# Final_5_2.net
KiCad netlist of a schematic drawn in EAGLE
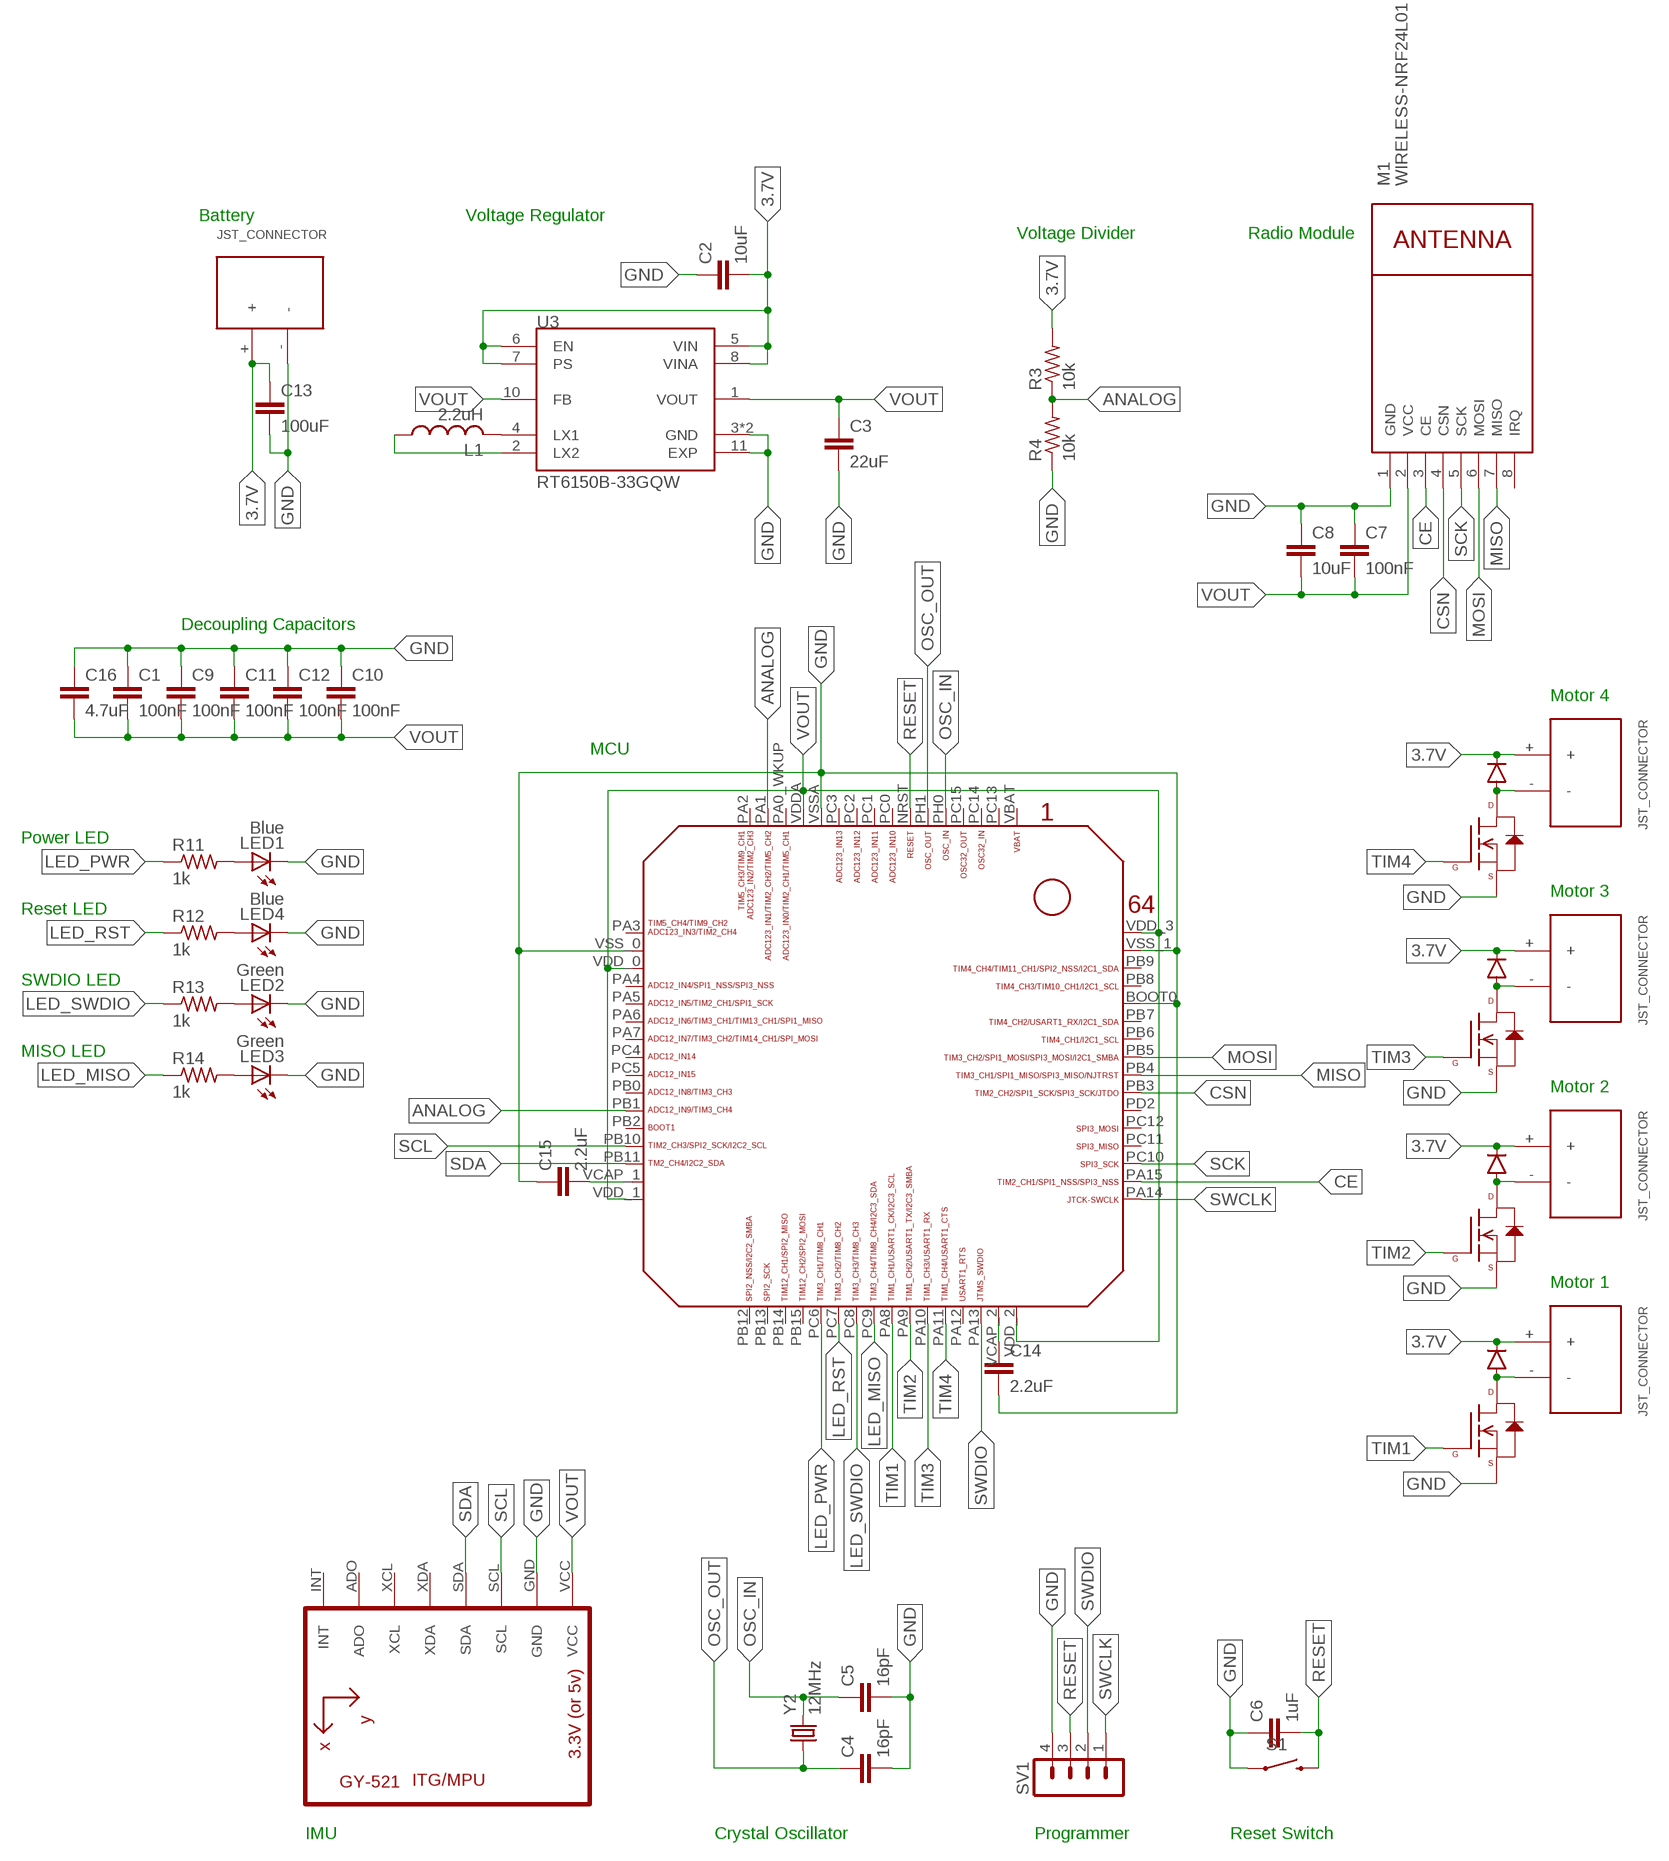
[diagram p0: schematic, sheet 1]

(export (version "E")
  (design (tool "Eeschema 10.0.6"))
  (components
    (comp (ref "C1")
      (value "100nF")
      (footprint "eagle-import:C0603")
      (libsource (lib "eagle-import") (part "rcl_334_C-EUC0603"))
    )
    (comp (ref "C2")
      (value "10uF")
      (footprint "eagle-import:C0603")
      (libsource (lib "eagle-import") (part "rcl_334_C-EUC0603"))
    )
    (comp (ref "C3")
      (value "22uF")
      (footprint "eagle-import:C0603")
      (libsource (lib "eagle-import") (part "rcl_334_C-EUC0603"))
    )
    (comp (ref "C4")
      (value "16pF")
      (footprint "eagle-import:C0603")
      (libsource (lib "eagle-import") (part "rcl_334_C-EUC0603"))
    )
    (comp (ref "C5")
      (value "16pF")
      (footprint "eagle-import:C0603")
      (libsource (lib "eagle-import") (part "rcl_334_C-EUC0603"))
    )
    (comp (ref "C6")
      (value "1uF")
      (footprint "eagle-import:C0603")
      (libsource (lib "eagle-import") (part "rcl_334_C-EUC0603"))
    )
    (comp (ref "C7")
      (value "100nF")
      (footprint "eagle-import:C0603")
      (libsource (lib "eagle-import") (part "rcl_334_C-EUC0603"))
    )
    (comp (ref "C8")
      (value "10uF")
      (footprint "eagle-import:C0603")
      (libsource (lib "eagle-import") (part "rcl_334_C-EUC0603"))
    )
    (comp (ref "C9")
      (value "100nF")
      (footprint "eagle-import:C0603")
      (libsource (lib "eagle-import") (part "rcl_334_C-EUC0603"))
    )
    (comp (ref "C10")
      (value "100nF")
      (footprint "eagle-import:C0603")
      (libsource (lib "eagle-import") (part "rcl_334_C-EUC0603"))
    )
    (comp (ref "C11")
      (value "100nF")
      (footprint "eagle-import:C0603")
      (libsource (lib "eagle-import") (part "rcl_334_C-EUC0603"))
    )
    (comp (ref "C12")
      (value "100nF")
      (footprint "eagle-import:C0603")
      (libsource (lib "eagle-import") (part "rcl_334_C-EUC0603"))
    )
    (comp (ref "C13")
      (value "100uF")
      (footprint "eagle-import:C1206")
      (libsource (lib "eagle-import") (part "rcl_334_C-EUC1206"))
    )
    (comp (ref "C14")
      (value "2.2uF")
      (footprint "eagle-import:C0603")
      (libsource (lib "eagle-import") (part "C-EUC0603"))
    )
    (comp (ref "C15")
      (value "2.2uF")
      (footprint "eagle-import:C0603")
      (libsource (lib "eagle-import") (part "C-EUC0603"))
    )
    (comp (ref "C16")
      (value "4.7uF")
      (footprint "eagle-import:C0603")
      (libsource (lib "eagle-import") (part "rcl_334_C-EUC0603"))
    )
    (comp (ref "L1")
      (value "2.2uH")
      (footprint "eagle-import:L0603")
      (libsource (lib "eagle-import") (part "L-USL0603"))
    )
    (comp (ref "LED1")
      (value "Blue")
      (footprint "eagle-import:CHIP-LED0603")
      (libsource (lib "eagle-import") (part "LEDCHIP-LED0603"))
    )
    (comp (ref "LED2")
      (value "Green")
      (footprint "eagle-import:CHIP-LED0603")
      (libsource (lib "eagle-import") (part "LEDCHIP-LED0603"))
    )
    (comp (ref "LED3")
      (value "Green")
      (footprint "eagle-import:CHIP-LED0603")
      (libsource (lib "eagle-import") (part "LEDCHIP-LED0603"))
    )
    (comp (ref "LED4")
      (value "Blue")
      (footprint "eagle-import:CHIP-LED0603")
      (libsource (lib "eagle-import") (part "LEDCHIP-LED0603"))
    )
    (comp (ref "M1")
      (value "WIRELESS-NRF24L01")
      (footprint "eagle-import:WIRELESS-NRF24L01")
      (libsource (lib "eagle-import") (part "WIRELESS-NRF24L01"))
    )
    (comp (ref "R3")
      (value "10k")
      (footprint "eagle-import:R0603")
      (libsource (lib "eagle-import") (part "R-US_R0603"))
    )
    (comp (ref "R4")
      (value "10k")
      (footprint "eagle-import:R0603")
      (libsource (lib "eagle-import") (part "R-US_R0603"))
    )
    (comp (ref "R11")
      (value "1k")
      (footprint "eagle-import:R0603")
      (libsource (lib "eagle-import") (part "R-US_R0603"))
    )
    (comp (ref "R12")
      (value "1k")
      (footprint "eagle-import:R0603")
      (libsource (lib "eagle-import") (part "R-US_R0603"))
    )
    (comp (ref "R13")
      (value "1k")
      (footprint "eagle-import:R0603")
      (libsource (lib "eagle-import") (part "R-US_R0603"))
    )
    (comp (ref "R14")
      (value "1k")
      (footprint "eagle-import:R0603")
      (libsource (lib "eagle-import") (part "R-US_R0603"))
    )
    (comp (ref "S1")
      (value "SWITCH-MOMENTARY-2SMD")
      (footprint "eagle-import:TACTILE-SWITCH-SMD")
      (libsource (lib "eagle-import") (part "SWITCH-MOMENTARY-2SMD"))
    )
    (comp (ref "SV1")
      (value "MA04-1")
      (footprint "eagle-import:MA04-1")
      (libsource (lib "eagle-import") (part "MA04-1"))
    )
    (comp (ref "U$1")
      (value "STM32F405/415_LQFP64")
      (footprint "eagle-import:STM32F405_415_LQFP64")
      (libsource (lib "eagle-import") (part "STM32F405/415_LQFP64"))
    )
    (comp (ref "U$2")
      (value "JST_CONNECTOR_FEMALE")
      (footprint "eagle-import:JST_CONNECTOR_FEMALE")
      (libsource (lib "eagle-import") (part "JST_CONNECTOR_FEMALE"))
    )
    (comp (ref "U$3")
      (value "JST_CONNECTOR_FEMALE")
      (footprint "eagle-import:JST_CONNECTOR_FEMALE")
      (libsource (lib "eagle-import") (part "JST_CONNECTOR_FEMALE"))
    )
    (comp (ref "U$4")
      (value "JST_CONNECTOR_FEMALE")
      (footprint "eagle-import:JST_CONNECTOR_FEMALE")
      (libsource (lib "eagle-import") (part "JST_CONNECTOR_FEMALE"))
    )
    (comp (ref "U$5")
      (value "JST_CONNECTOR_FEMALE")
      (footprint "eagle-import:JST_CONNECTOR_FEMALE")
      (libsource (lib "eagle-import") (part "JST_CONNECTOR_FEMALE"))
    )
    (comp (ref "U$6")
      (value "JST_CONNECTOR_FEMALE")
      (footprint "eagle-import:JST_CONNECTOR_FEMALE")
      (libsource (lib "eagle-import") (part "JST_CONNECTOR_FEMALE"))
    )
    (comp (ref "U$7")
      (value "N-CHANNEL-MOSFET-IRLML6244TRPBF")
      (footprint "eagle-import:SOT23-3")
      (libsource (lib "eagle-import") (part "N-CHANNEL-MOSFET-IRLML6244TRPBF"))
    )
    (comp (ref "U$8")
      (value "N-CHANNEL-MOSFET-IRLML6244TRPBF")
      (footprint "eagle-import:SOT23-3")
      (libsource (lib "eagle-import") (part "N-CHANNEL-MOSFET-IRLML6244TRPBF"))
    )
    (comp (ref "U$9")
      (value "N-CHANNEL-MOSFET-IRLML6244TRPBF")
      (footprint "eagle-import:SOT23-3")
      (libsource (lib "eagle-import") (part "N-CHANNEL-MOSFET-IRLML6244TRPBF"))
    )
    (comp (ref "U$10")
      (value "N-CHANNEL-MOSFET-IRLML6244TRPBF")
      (footprint "eagle-import:SOT23-3")
      (libsource (lib "eagle-import") (part "N-CHANNEL-MOSFET-IRLML6244TRPBF"))
    )
    (comp (ref "U$11")
      (value "DB2W40300L")
      (footprint "eagle-import:MINI2-F3-B")
      (libsource (lib "eagle-import") (part "DB2W40300L"))
    )
    (comp (ref "U$12")
      (value "DB2W40300L")
      (footprint "eagle-import:MINI2-F3-B")
      (libsource (lib "eagle-import") (part "DB2W40300L"))
    )
    (comp (ref "U$13")
      (value "DB2W40300L")
      (footprint "eagle-import:MINI2-F3-B")
      (libsource (lib "eagle-import") (part "DB2W40300L"))
    )
    (comp (ref "U$14")
      (value "DB2W40300L")
      (footprint "eagle-import:MINI2-F3-B")
      (libsource (lib "eagle-import") (part "DB2W40300L"))
    )
    (comp (ref "U2")
      (value "GY-521MPU6050")
      (footprint "eagle-import:GY-521")
      (libsource (lib "eagle-import") (part "GY-521MPU6050"))
    )
    (comp (ref "U3")
      (value "RT6150B-33GQW")
      (footprint "eagle-import:SON50P250X250X80-11N")
      (fields (field (name "DIGI-KEY_PART_NUMBER") "RT6150B-33GQWCT-ND") (field (name "MF") "Richtek USA"))
      (libsource (lib "eagle-import") (part "RT6150B-33GQW"))
    )
    (comp (ref "Y2")
      (value "12MHz")
      (footprint "eagle-import:HC49UP")
      (libsource (lib "eagle-import") (part "CRYSTALSMD"))
    )
  )
  (nets
    (net (code "1") (name "3.7V") (class "Default")
      (node (ref "C13") (pin "1") (pinfunction "1_1") (pintype "passive"))
      (node (ref "C2") (pin "2") (pinfunction "2_2") (pintype "passive"))
      (node (ref "R3") (pin "2") (pinfunction "2_2") (pintype "passive"))
      (node (ref "U$11") (pin "NEG") (pinfunction "GPIN_NEG") (pintype "passive"))
      (node (ref "U$12") (pin "NEG") (pinfunction "GPIN_NEG") (pintype "passive"))
      (node (ref "U$13") (pin "NEG") (pinfunction "GPIN_NEG") (pintype "passive"))
      (node (ref "U$14") (pin "NEG") (pinfunction "GPIN_NEG") (pintype "passive"))
      (node (ref "U$2") (pin "+") (pinfunction "+_+") (pintype "bidirectional"))
      (node (ref "U$3") (pin "+") (pinfunction "+_+") (pintype "bidirectional"))
      (node (ref "U$4") (pin "+") (pinfunction "+_+") (pintype "bidirectional"))
      (node (ref "U$5") (pin "+") (pinfunction "+_+") (pintype "bidirectional"))
      (node (ref "U$6") (pin "+") (pinfunction "+_+") (pintype "bidirectional"))
      (node (ref "U3") (pin "5") (pinfunction "VIN_5") (pintype "power_in"))
      (node (ref "U3") (pin "6") (pinfunction "EN_6") (pintype "input"))
      (node (ref "U3") (pin "7") (pinfunction "PS_7") (pintype "input"))
      (node (ref "U3") (pin "8") (pinfunction "VINA_8") (pintype "power_in"))
    )
    (net (code "2") (name "ANALOG") (class "Default")
      (node (ref "R3") (pin "1") (pinfunction "1_1") (pintype "passive"))
      (node (ref "R4") (pin "2") (pinfunction "2_2") (pintype "passive"))
      (node (ref "U$1") (pin "PA1") (pinfunction "PA1_PA1") (pintype "bidirectional"))
      (node (ref "U$1") (pin "PB1") (pinfunction "PB1_PB1") (pintype "bidirectional"))
    )
    (net (code "3") (name "CE") (class "Default")
      (node (ref "M1") (pin "3") (pinfunction "CE_3") (pintype "bidirectional"))
      (node (ref "U$1") (pin "PA15") (pinfunction "PA15_PA15") (pintype "bidirectional"))
    )
    (net (code "4") (name "CSN") (class "Default")
      (node (ref "M1") (pin "4") (pinfunction "CSN_4") (pintype "bidirectional"))
      (node (ref "U$1") (pin "PB3") (pinfunction "PB3_PB3") (pintype "bidirectional"))
    )
    (net (code "5") (name "GND") (class "Default")
      (node (ref "C1") (pin "1") (pinfunction "1_1") (pintype "passive"))
      (node (ref "C10") (pin "1") (pinfunction "1_1") (pintype "passive"))
      (node (ref "C11") (pin "1") (pinfunction "1_1") (pintype "passive"))
      (node (ref "C12") (pin "1") (pinfunction "1_1") (pintype "passive"))
      (node (ref "C13") (pin "2") (pinfunction "2_2") (pintype "passive"))
      (node (ref "C14") (pin "2") (pinfunction "2_2") (pintype "passive"))
      (node (ref "C15") (pin "1") (pinfunction "1_1") (pintype "passive"))
      (node (ref "C16") (pin "1") (pinfunction "1_1") (pintype "passive"))
      (node (ref "C2") (pin "1") (pinfunction "1_1") (pintype "passive"))
      (node (ref "C3") (pin "2") (pinfunction "2_2") (pintype "passive"))
      (node (ref "C4") (pin "2") (pinfunction "2_2") (pintype "passive"))
      (node (ref "C5") (pin "2") (pinfunction "2_2") (pintype "passive"))
      (node (ref "C6") (pin "1") (pinfunction "1_1") (pintype "passive"))
      (node (ref "C7") (pin "1") (pinfunction "1_1") (pintype "passive"))
      (node (ref "C8") (pin "1") (pinfunction "1_1") (pintype "passive"))
      (node (ref "C9") (pin "1") (pinfunction "1_1") (pintype "passive"))
      (node (ref "LED1") (pin "C") (pinfunction "C_C") (pintype "passive"))
      (node (ref "LED2") (pin "C") (pinfunction "C_C") (pintype "passive"))
      (node (ref "LED3") (pin "C") (pinfunction "C_C") (pintype "passive"))
      (node (ref "LED4") (pin "C") (pinfunction "C_C") (pintype "passive"))
      (node (ref "M1") (pin "1") (pinfunction "GND_1") (pintype "power_in"))
      (node (ref "R4") (pin "1") (pinfunction "1_1") (pintype "passive"))
      (node (ref "S1") (pin "1") (pinfunction "1_1") (pintype "passive"))
      (node (ref "SV1") (pin "4") (pinfunction "4_4") (pintype "passive"))
      (node (ref "U$1") (pin "BOOT0") (pinfunction "BOOT0_BOOT0") (pintype "bidirectional"))
      (node (ref "U$1") (pin "VSSA") (pinfunction "VSSA_VSSA") (pintype "bidirectional"))
      (node (ref "U$1") (pin "VSS_0") (pinfunction "VSS_0_VSS_0") (pintype "bidirectional"))
      (node (ref "U$1") (pin "VSS_1") (pinfunction "VSS_1_VSS_1") (pintype "bidirectional"))
      (node (ref "U$10") (pin "2") (pinfunction "S_2") (pintype "passive"))
      (node (ref "U$2") (pin "-") (pinfunction "-_-") (pintype "bidirectional"))
      (node (ref "U$7") (pin "2") (pinfunction "S_2") (pintype "passive"))
      (node (ref "U$8") (pin "2") (pinfunction "S_2") (pintype "passive"))
      (node (ref "U$9") (pin "2") (pinfunction "S_2") (pintype "passive"))
      (node (ref "U2") (pin "GND") (pinfunction "GND_GND") (pintype "bidirectional"))
      (node (ref "U3") (pin "11") (pinfunction "EXP_11") (pintype "passive"))
      (node (ref "U3") (pin "3") (pinfunction "GND_3") (pintype "power_in"))
      (node (ref "U3") (pin "9") (pinfunction "GND_9") (pintype "power_in"))
    )
    (net (code "6") (name "LED_MISO") (class "Default")
      (node (ref "R14") (pin "1") (pinfunction "1_1") (pintype "passive"))
      (node (ref "U$1") (pin "PC9") (pinfunction "PC9_PC9") (pintype "bidirectional"))
    )
    (net (code "7") (name "LED_PWR") (class "Default")
      (node (ref "R11") (pin "1") (pinfunction "1_1") (pintype "passive"))
      (node (ref "U$1") (pin "PC6") (pinfunction "PC6_PC6") (pintype "bidirectional"))
    )
    (net (code "8") (name "LED_RST") (class "Default")
      (node (ref "R12") (pin "1") (pinfunction "1_1") (pintype "passive"))
      (node (ref "U$1") (pin "PC7") (pinfunction "PC7_PC7") (pintype "bidirectional"))
    )
    (net (code "9") (name "LED_SWDIO") (class "Default")
      (node (ref "R13") (pin "1") (pinfunction "1_1") (pintype "passive"))
      (node (ref "U$1") (pin "PC8") (pinfunction "PC8_PC8") (pintype "bidirectional"))
    )
    (net (code "10") (name "MISO") (class "Default")
      (node (ref "M1") (pin "7") (pinfunction "MISO_7") (pintype "bidirectional"))
      (node (ref "U$1") (pin "PB4") (pinfunction "PB4_PB4") (pintype "bidirectional"))
    )
    (net (code "11") (name "MOSI") (class "Default")
      (node (ref "M1") (pin "6") (pinfunction "MOSI_6") (pintype "bidirectional"))
      (node (ref "U$1") (pin "PB5") (pinfunction "PB5_PB5") (pintype "bidirectional"))
    )
    (net (code "12") (name "Net-(C14-Pad1)") (class "Default")
      (node (ref "C14") (pin "1") (pinfunction "1_1") (pintype "passive"))
      (node (ref "U$1") (pin "VCAP_2") (pinfunction "VCAP_2_VCAP_2") (pintype "bidirectional"))
    )
    (net (code "13") (name "Net-(C15-Pad2)") (class "Default")
      (node (ref "C15") (pin "2") (pinfunction "2_2") (pintype "passive"))
      (node (ref "U$1") (pin "VCAP_1") (pinfunction "VCAP_1_VCAP_1") (pintype "bidirectional"))
    )
    (net (code "14") (name "Net-(LED1-PadA)") (class "Default")
      (node (ref "LED1") (pin "A") (pinfunction "A_A") (pintype "passive"))
      (node (ref "R11") (pin "2") (pinfunction "2_2") (pintype "passive"))
    )
    (net (code "15") (name "Net-(LED2-PadA)") (class "Default")
      (node (ref "LED2") (pin "A") (pinfunction "A_A") (pintype "passive"))
      (node (ref "R13") (pin "2") (pinfunction "2_2") (pintype "passive"))
    )
    (net (code "16") (name "Net-(LED3-PadA)") (class "Default")
      (node (ref "LED3") (pin "A") (pinfunction "A_A") (pintype "passive"))
      (node (ref "R14") (pin "2") (pinfunction "2_2") (pintype "passive"))
    )
    (net (code "17") (name "Net-(LED4-PadA)") (class "Default")
      (node (ref "LED4") (pin "A") (pinfunction "A_A") (pintype "passive"))
      (node (ref "R12") (pin "2") (pinfunction "2_2") (pintype "passive"))
    )
    (net (code "18") (name "Net-(U$10-D)") (class "Default")
      (node (ref "U$10") (pin "3") (pinfunction "D_3") (pintype "passive"))
      (node (ref "U$14") (pin "POS") (pinfunction "PPIN_POS") (pintype "passive"))
      (node (ref "U$6") (pin "-") (pinfunction "-_-") (pintype "bidirectional"))
    )
    (net (code "19") (name "Net-(U$11-PPIN)") (class "Default")
      (node (ref "U$11") (pin "POS") (pinfunction "PPIN_POS") (pintype "passive"))
      (node (ref "U$3") (pin "-") (pinfunction "-_-") (pintype "bidirectional"))
      (node (ref "U$9") (pin "3") (pinfunction "D_3") (pintype "passive"))
    )
    (net (code "20") (name "Net-(U$12-PPIN)") (class "Default")
      (node (ref "U$12") (pin "POS") (pinfunction "PPIN_POS") (pintype "passive"))
      (node (ref "U$5") (pin "-") (pinfunction "-_-") (pintype "bidirectional"))
      (node (ref "U$8") (pin "3") (pinfunction "D_3") (pintype "passive"))
    )
    (net (code "21") (name "Net-(U$13-PPIN)") (class "Default")
      (node (ref "U$13") (pin "POS") (pinfunction "PPIN_POS") (pintype "passive"))
      (node (ref "U$4") (pin "-") (pinfunction "-_-") (pintype "bidirectional"))
      (node (ref "U$7") (pin "3") (pinfunction "D_3") (pintype "passive"))
    )
    (net (code "22") (name "Net-(U3-LX1)") (class "Default")
      (node (ref "L1") (pin "2") (pinfunction "2_2") (pintype "passive"))
      (node (ref "U3") (pin "4") (pinfunction "LX1_4") (pintype "passive"))
    )
    (net (code "23") (name "Net-(U3-LX2)") (class "Default")
      (node (ref "L1") (pin "1") (pinfunction "1_1") (pintype "passive"))
      (node (ref "U3") (pin "2") (pinfunction "LX2_2") (pintype "passive"))
    )
    (net (code "24") (name "OSC_IN") (class "Default")
      (node (ref "C5") (pin "1") (pinfunction "1_1") (pintype "passive"))
      (node (ref "U$1") (pin "PH0") (pinfunction "PH0_PH0") (pintype "bidirectional"))
      (node (ref "Y2") (pin "2") (pinfunction "2_2") (pintype "passive"))
    )
    (net (code "25") (name "OSC_OUT") (class "Default")
      (node (ref "C4") (pin "1") (pinfunction "1_1") (pintype "passive"))
      (node (ref "U$1") (pin "PH1") (pinfunction "PH1_PH1") (pintype "bidirectional"))
      (node (ref "Y2") (pin "1") (pinfunction "1_1") (pintype "passive"))
    )
    (net (code "26") (name "RESET") (class "Default")
      (node (ref "C6") (pin "2") (pinfunction "2_2") (pintype "passive"))
      (node (ref "S1") (pin "3") (pinfunction "2_3") (pintype "passive"))
      (node (ref "SV1") (pin "3") (pinfunction "3_3") (pintype "passive"))
      (node (ref "U$1") (pin "NRST") (pinfunction "NRST_NRST") (pintype "bidirectional"))
    )
    (net (code "27") (name "SCK") (class "Default")
      (node (ref "M1") (pin "5") (pinfunction "SCK_5") (pintype "bidirectional"))
      (node (ref "U$1") (pin "PC10") (pinfunction "PC10_PC10") (pintype "bidirectional"))
    )
    (net (code "28") (name "SCL") (class "Default")
      (node (ref "U$1") (pin "PB10") (pinfunction "PB10_PB10") (pintype "bidirectional"))
      (node (ref "U2") (pin "SCL") (pinfunction "SCL_SCL") (pintype "bidirectional"))
    )
    (net (code "29") (name "SDA") (class "Default")
      (node (ref "U$1") (pin "PB11") (pinfunction "PB11_PB11") (pintype "bidirectional"))
      (node (ref "U2") (pin "SDA") (pinfunction "SDA_SDA") (pintype "bidirectional"))
    )
    (net (code "30") (name "SWCLK") (class "Default")
      (node (ref "SV1") (pin "1") (pinfunction "1_1") (pintype "passive"))
      (node (ref "U$1") (pin "PA14") (pinfunction "PA14_PA14") (pintype "bidirectional"))
    )
    (net (code "31") (name "SWDIO") (class "Default")
      (node (ref "SV1") (pin "2") (pinfunction "2_2") (pintype "passive"))
      (node (ref "U$1") (pin "PA13") (pinfunction "PA13_PA13") (pintype "bidirectional"))
    )
    (net (code "32") (name "TIM1") (class "Default")
      (node (ref "U$1") (pin "PA8") (pinfunction "PA8_PA8") (pintype "bidirectional"))
      (node (ref "U$10") (pin "1") (pinfunction "G_1") (pintype "passive"))
    )
    (net (code "33") (name "TIM2") (class "Default")
      (node (ref "U$1") (pin "PA9") (pinfunction "PA9_PA9") (pintype "bidirectional"))
      (node (ref "U$8") (pin "1") (pinfunction "G_1") (pintype "passive"))
    )
    (net (code "34") (name "TIM3") (class "Default")
      (node (ref "U$1") (pin "PA10") (pinfunction "PA10_PA10") (pintype "bidirectional"))
      (node (ref "U$7") (pin "1") (pinfunction "G_1") (pintype "passive"))
    )
    (net (code "35") (name "TIM4") (class "Default")
      (node (ref "U$1") (pin "PA11") (pinfunction "PA11_PA11") (pintype "bidirectional"))
      (node (ref "U$9") (pin "1") (pinfunction "G_1") (pintype "passive"))
    )
    (net (code "36") (name "VOUT") (class "Default")
      (node (ref "C1") (pin "2") (pinfunction "2_2") (pintype "passive"))
      (node (ref "C10") (pin "2") (pinfunction "2_2") (pintype "passive"))
      (node (ref "C11") (pin "2") (pinfunction "2_2") (pintype "passive"))
      (node (ref "C12") (pin "2") (pinfunction "2_2") (pintype "passive"))
      (node (ref "C16") (pin "2") (pinfunction "2_2") (pintype "passive"))
      (node (ref "C3") (pin "1") (pinfunction "1_1") (pintype "passive"))
      (node (ref "C7") (pin "2") (pinfunction "2_2") (pintype "passive"))
      (node (ref "C8") (pin "2") (pinfunction "2_2") (pintype "passive"))
      (node (ref "C9") (pin "2") (pinfunction "2_2") (pintype "passive"))
      (node (ref "M1") (pin "2") (pinfunction "VCC_2") (pintype "power_in"))
      (node (ref "U$1") (pin "VDDA") (pinfunction "VDDA_VDDA") (pintype "bidirectional"))
      (node (ref "U$1") (pin "VDD_0") (pinfunction "VDD_0_VDD_0") (pintype "bidirectional"))
      (node (ref "U$1") (pin "VDD_1") (pinfunction "VDD_1_VDD_1") (pintype "bidirectional"))
      (node (ref "U$1") (pin "VDD_2") (pinfunction "VDD_2_VDD_2") (pintype "bidirectional"))
      (node (ref "U$1") (pin "VDD_3") (pinfunction "VDD_3_VDD_3") (pintype "bidirectional"))
      (node (ref "U2") (pin "VCC") (pinfunction "VCC_VCC") (pintype "bidirectional"))
      (node (ref "U3") (pin "1") (pinfunction "VOUT_1") (pintype "output"))
      (node (ref "U3") (pin "10") (pinfunction "FB_10") (pintype "input"))
    )
    (net (code "37") (name "unconnected-(M1-IRQ-Pad8)") (class "Default")
      (node (ref "M1") (pin "8") (pinfunction "IRQ_8") (pintype "bidirectional"))
    )
    (net (code "38") (name "unconnected-(U$1-PA0_AKUP-PadPA0_WKUP)") (class "Default")
      (node (ref "U$1") (pin "PA0_WKUP") (pinfunction "PA0_AKUP_PA0_WKUP") (pintype "bidirectional"))
    )
    (net (code "39") (name "unconnected-(U$1-PadPA2)") (class "Default")
      (node (ref "U$1") (pin "PA2") (pinfunction "PA2_PA2") (pintype "bidirectional"))
    )
    (net (code "40") (name "unconnected-(U$1-PadPA3)") (class "Default")
      (node (ref "U$1") (pin "PA3") (pinfunction "PA3_PA3") (pintype "bidirectional"))
    )
    (net (code "41") (name "unconnected-(U$1-PadPA4)") (class "Default")
      (node (ref "U$1") (pin "PA4") (pinfunction "PA4_PA4") (pintype "bidirectional"))
    )
    (net (code "42") (name "unconnected-(U$1-PadPA5)") (class "Default")
      (node (ref "U$1") (pin "PA5") (pinfunction "PA5_PA5") (pintype "bidirectional"))
    )
    (net (code "43") (name "unconnected-(U$1-PadPA6)") (class "Default")
      (node (ref "U$1") (pin "PA6") (pinfunction "PA6_PA6") (pintype "bidirectional"))
    )
    (net (code "44") (name "unconnected-(U$1-PadPA7)") (class "Default")
      (node (ref "U$1") (pin "PA7") (pinfunction "PA7_PA7") (pintype "bidirectional"))
    )
    (net (code "45") (name "unconnected-(U$1-PadPA12)") (class "Default")
      (node (ref "U$1") (pin "PA12") (pinfunction "PA12_PA12") (pintype "bidirectional"))
    )
    (net (code "46") (name "unconnected-(U$1-PadPB0)") (class "Default")
      (node (ref "U$1") (pin "PB0") (pinfunction "PB0_PB0") (pintype "bidirectional"))
    )
    (net (code "47") (name "unconnected-(U$1-PadPB2)") (class "Default")
      (node (ref "U$1") (pin "PB2") (pinfunction "PB2_PB2") (pintype "bidirectional"))
    )
    (net (code "48") (name "unconnected-(U$1-PadPB6)") (class "Default")
      (node (ref "U$1") (pin "PB6") (pinfunction "PB6_PB6") (pintype "bidirectional"))
    )
    (net (code "49") (name "unconnected-(U$1-PadPB7)") (class "Default")
      (node (ref "U$1") (pin "PB7") (pinfunction "PB7_PB7") (pintype "bidirectional"))
    )
    (net (code "50") (name "unconnected-(U$1-PadPB8)") (class "Default")
      (node (ref "U$1") (pin "PB8") (pinfunction "PB8_PB8") (pintype "bidirectional"))
    )
    (net (code "51") (name "unconnected-(U$1-PadPB9)") (class "Default")
      (node (ref "U$1") (pin "PB9") (pinfunction "PB9_PB9") (pintype "bidirectional"))
    )
    (net (code "52") (name "unconnected-(U$1-PadPB12)") (class "Default")
      (node (ref "U$1") (pin "PB12") (pinfunction "PB12_PB12") (pintype "bidirectional"))
    )
    (net (code "53") (name "unconnected-(U$1-PadPB13)") (class "Default")
      (node (ref "U$1") (pin "PB13") (pinfunction "PB13_PB13") (pintype "bidirectional"))
    )
    (net (code "54") (name "unconnected-(U$1-PadPB14)") (class "Default")
      (node (ref "U$1") (pin "PB14") (pinfunction "PB14_PB14") (pintype "bidirectional"))
    )
    (net (code "55") (name "unconnected-(U$1-PadPB15)") (class "Default")
      (node (ref "U$1") (pin "PB15") (pinfunction "PB15_PB15") (pintype "bidirectional"))
    )
    (net (code "56") (name "unconnected-(U$1-PadPC0)") (class "Default")
      (node (ref "U$1") (pin "PC0") (pinfunction "PC0_PC0") (pintype "bidirectional"))
    )
    (net (code "57") (name "unconnected-(U$1-PadPC1)") (class "Default")
      (node (ref "U$1") (pin "PC1") (pinfunction "PC1_PC1") (pintype "bidirectional"))
    )
    (net (code "58") (name "unconnected-(U$1-PadPC2)") (class "Default")
      (node (ref "U$1") (pin "PC2") (pinfunction "PC2_PC2") (pintype "bidirectional"))
    )
    (net (code "59") (name "unconnected-(U$1-PadPC3)") (class "Default")
      (node (ref "U$1") (pin "PC3") (pinfunction "PC3_PC3") (pintype "bidirectional"))
    )
    (net (code "60") (name "unconnected-(U$1-PadPC4)") (class "Default")
      (node (ref "U$1") (pin "PC4") (pinfunction "PC4_PC4") (pintype "bidirectional"))
    )
    (net (code "61") (name "unconnected-(U$1-PadPC5)") (class "Default")
      (node (ref "U$1") (pin "PC5") (pinfunction "PC5_PC5") (pintype "bidirectional"))
    )
    (net (code "62") (name "unconnected-(U$1-PadPC11)") (class "Default")
      (node (ref "U$1") (pin "PC11") (pinfunction "PC11_PC11") (pintype "bidirectional"))
    )
    (net (code "63") (name "unconnected-(U$1-PadPC12)") (class "Default")
      (node (ref "U$1") (pin "PC12") (pinfunction "PC12_PC12") (pintype "bidirectional"))
    )
    (net (code "64") (name "unconnected-(U$1-PadPC13)") (class "Default")
      (node (ref "U$1") (pin "PC13") (pinfunction "PC13_PC13") (pintype "bidirectional"))
    )
    (net (code "65") (name "unconnected-(U$1-PadPC14)") (class "Default")
      (node (ref "U$1") (pin "PC14") (pinfunction "PC14_PC14") (pintype "bidirectional"))
    )
    (net (code "66") (name "unconnected-(U$1-PadPC15)") (class "Default")
      (node (ref "U$1") (pin "PC15") (pinfunction "PC15_PC15") (pintype "bidirectional"))
    )
    (net (code "67") (name "unconnected-(U$1-PadPD2)") (class "Default")
      (node (ref "U$1") (pin "PD2") (pinfunction "PD2_PD2") (pintype "bidirectional"))
    )
    (net (code "68") (name "unconnected-(U$1-PadVBAT)") (class "Default")
      (node (ref "U$1") (pin "VBAT") (pinfunction "VBAT_VBAT") (pintype "bidirectional"))
    )
    (net (code "69") (name "unconnected-(U2-PadADO)") (class "Default")
      (node (ref "U2") (pin "ADO") (pinfunction "ADO_ADO") (pintype "bidirectional"))
    )
    (net (code "70") (name "unconnected-(U2-PadINT)") (class "Default")
      (node (ref "U2") (pin "INT") (pinfunction "INT_INT") (pintype "bidirectional"))
    )
    (net (code "71") (name "unconnected-(U2-PadXCL)") (class "Default")
      (node (ref "U2") (pin "XCL") (pinfunction "XCL_XCL") (pintype "bidirectional"))
    )
    (net (code "72") (name "unconnected-(U2-PadXDA)") (class "Default")
      (node (ref "U2") (pin "XDA") (pinfunction "XDA_XDA") (pintype "bidirectional"))
    )
  )
)
